# interface.net
KiCad netlist of a schematic drawn in EAGLE
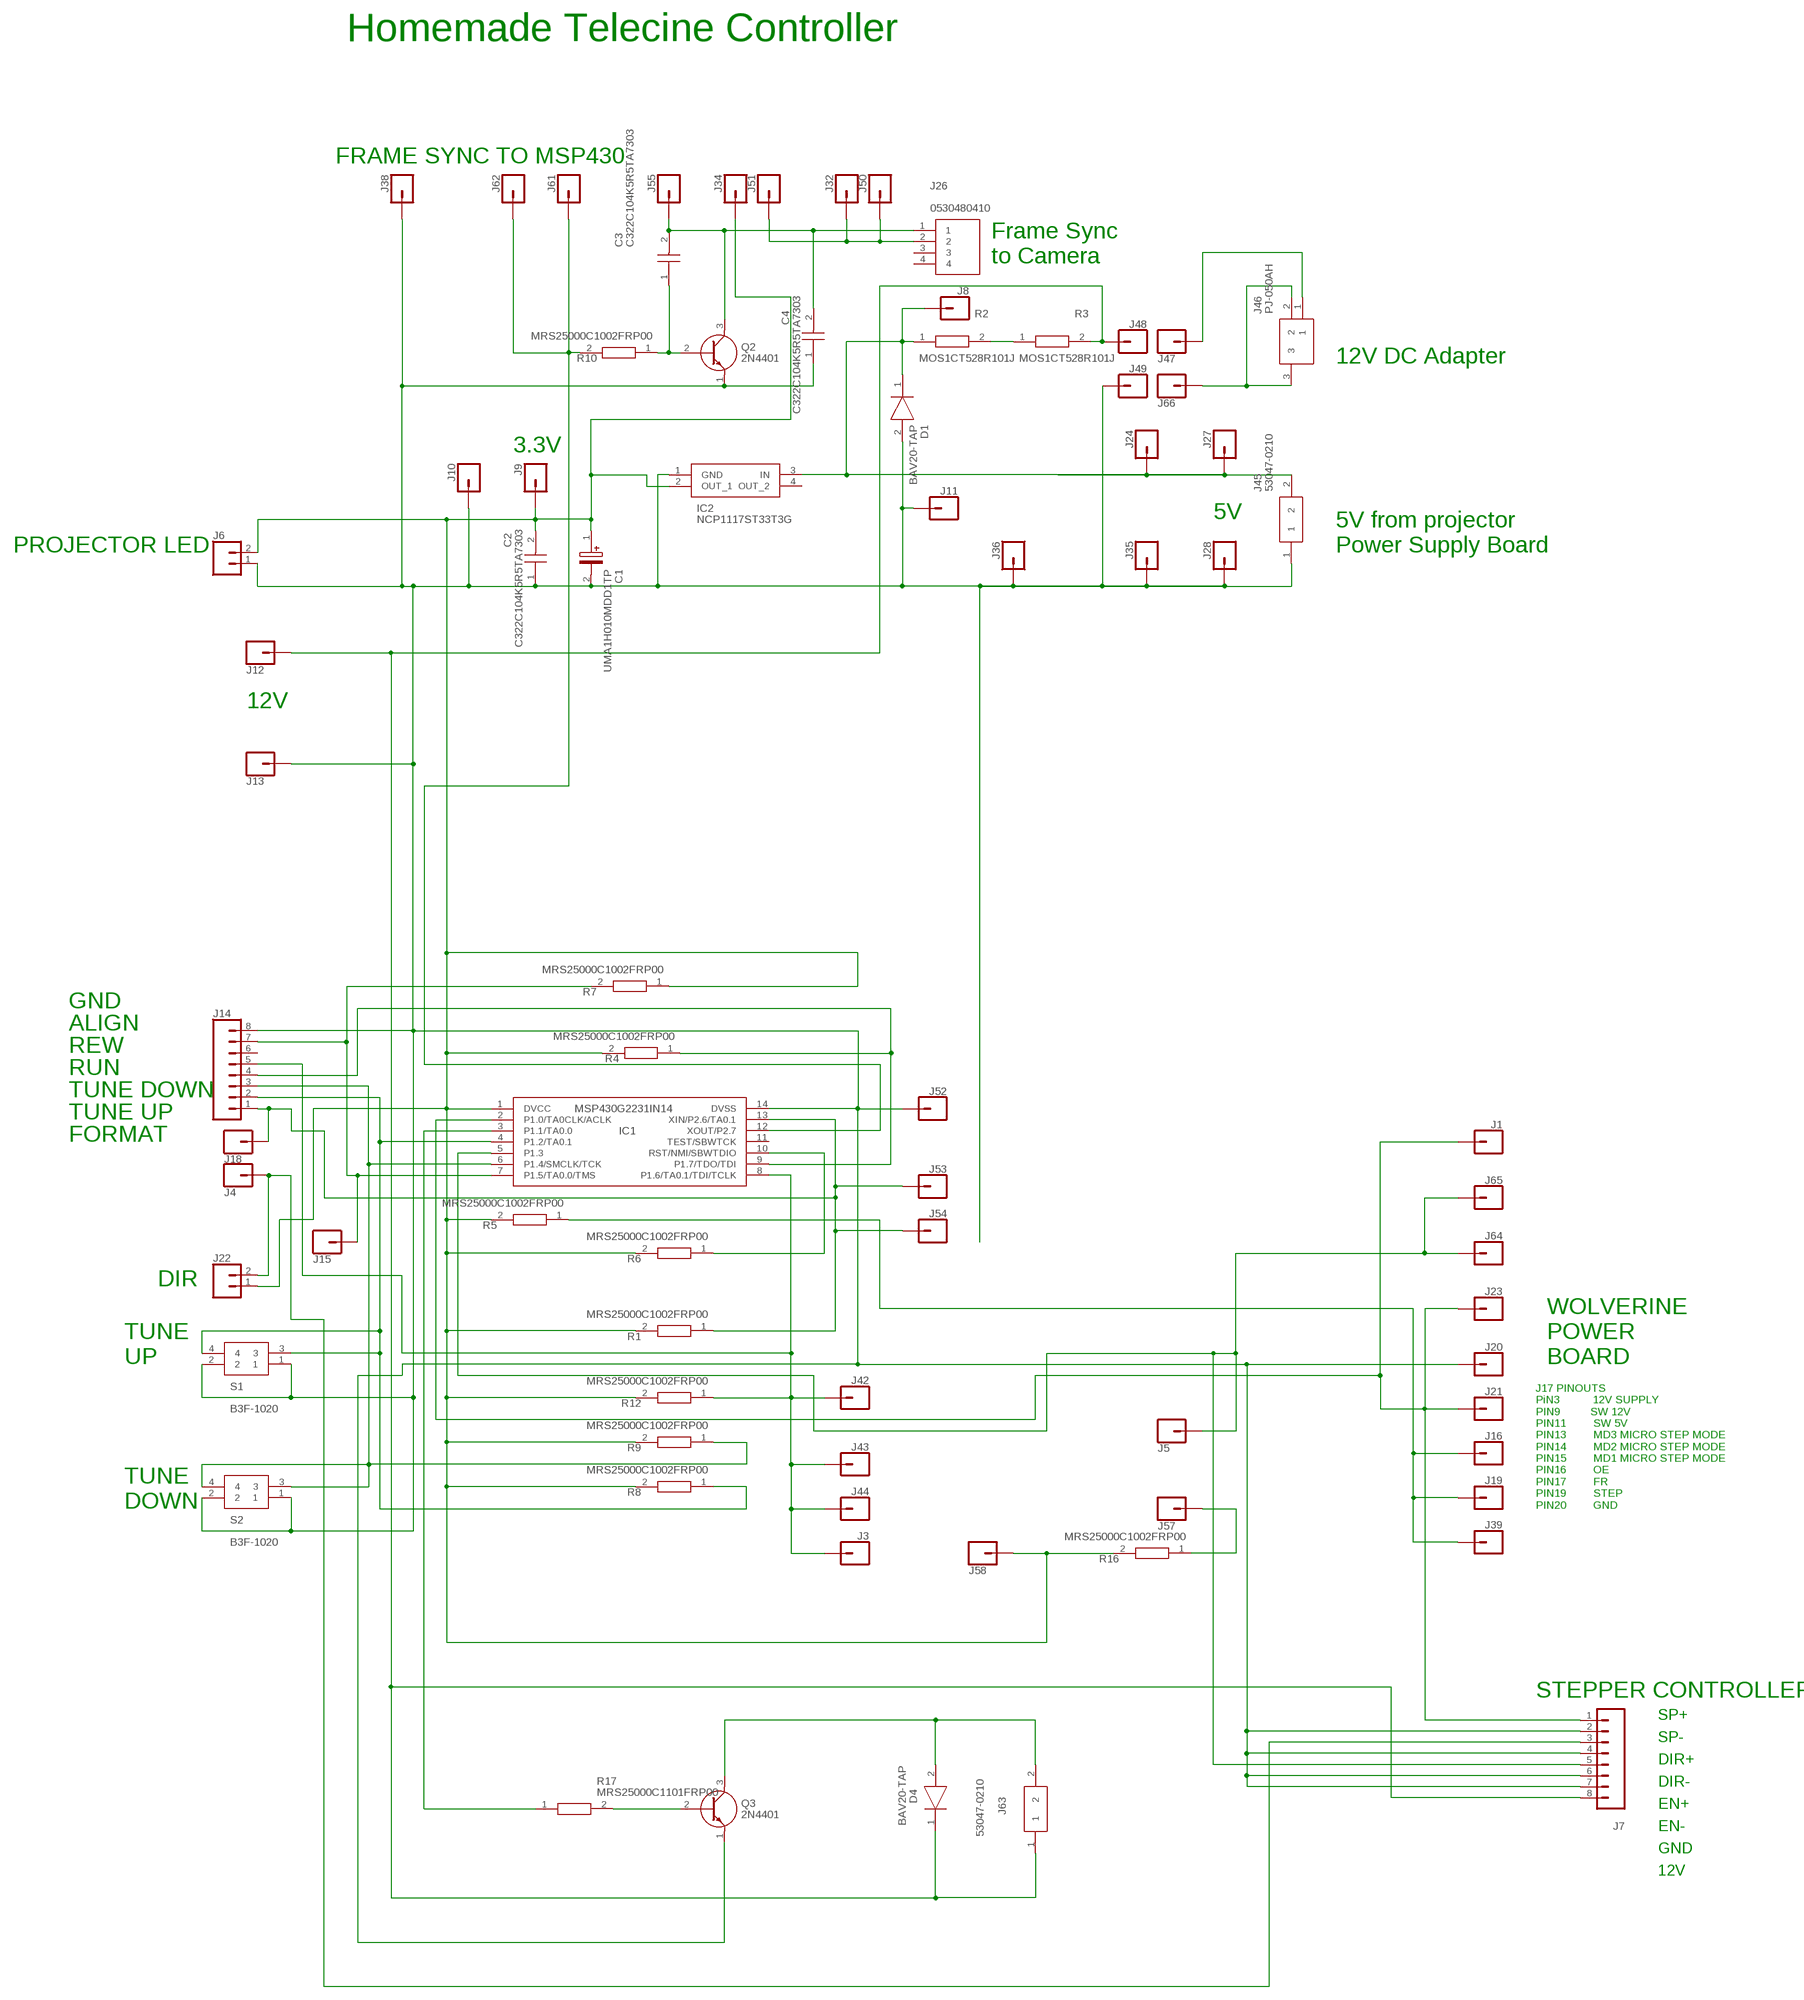
[diagram p0: schematic, sheet 1]

(export (version "E")
  (design (tool "Eeschema 10.0.6"))
  (components
    (comp (ref "C1")
      (value "UMA1H010MDD1TP")
      (footprint "eagle-import:CAPPRD150W45D450H600")
      (fields (field (name "MOUSER_PART_NUMBER") "647-UMA1H010MDD1TP"))
      (libsource (lib "eagle-import") (part "UMA1H010MDD1TP"))
    )
    (comp (ref "C2")
      (value "C322C104K5R5TA7303")
      (footprint "eagle-import:C322")
      (fields (field (name "MOUSER_PART_NUMBER") "80-C322C104K5R7303"))
      (libsource (lib "eagle-import") (part "C322C104K5R5TA7303"))
    )
    (comp (ref "C3")
      (value "C322C104K5R5TA7303")
      (footprint "eagle-import:C322")
      (fields (field (name "MOUSER_PART_NUMBER") "80-C322C104K5R7303"))
      (libsource (lib "eagle-import") (part "C322C104K5R5TA7303"))
    )
    (comp (ref "C4")
      (value "C322C104K5R5TA7303")
      (footprint "eagle-import:C322")
      (fields (field (name "MOUSER_PART_NUMBER") "80-C322C104K5R7303"))
      (libsource (lib "eagle-import") (part "C322C104K5R5TA7303"))
    )
    (comp (ref "D1")
      (value "BAV20-TAP")
      (footprint "eagle-import:DIOAD950W60L350D150")
      (fields (field (name "MOUSER_PART_NUMBER") "78-BAV20-TAP"))
      (libsource (lib "eagle-import") (part "BAV20-TAP"))
    )
    (comp (ref "D4")
      (value "BAV20-TAP")
      (footprint "eagle-import:DIOAD950W60L350D150")
      (fields (field (name "MOUSER_PART_NUMBER") "78-BAV20-TAP"))
      (libsource (lib "eagle-import") (part "BAV20-TAP"))
    )
    (comp (ref "IC1")
      (value "MSP430G2231IN14")
      (footprint "eagle-import:DIP254P762X508-14")
      (fields
        (field (name "MOUSER_PART_NUMBER") "595-MSP430G2231IN14")
        (field (name "RS_PART_NUMBER") "7244654P")
      )
      (libsource (lib "eagle-import") (part "MSP430G2231IN14"))
    )
    (comp (ref "IC2")
      (value "NCP1117ST33T3G")
      (footprint "eagle-import:SOT230P700X180-4N")
      (fields (field (name "MOUSER_PART_NUMBER") "863-NCP1117ST33T3G"))
      (libsource (lib "eagle-import") (part "NCP1117ST33T3G"))
    )
    (comp (ref "J1")
      (value "CONN_01")
      (footprint "eagle-import:1X01")
      (libsource (lib "eagle-import") (part "CONN_01"))
    )
    (comp (ref "J3")
      (value "CONN_01")
      (footprint "eagle-import:1X01")
      (libsource (lib "eagle-import") (part "CONN_01"))
    )
    (comp (ref "J4")
      (value "CONN_01")
      (footprint "eagle-import:1X01")
      (libsource (lib "eagle-import") (part "CONN_01"))
    )
    (comp (ref "J5")
      (value "CONN_01")
      (footprint "eagle-import:1X01")
      (libsource (lib "eagle-import") (part "CONN_01"))
    )
    (comp (ref "J6")
      (value "CONN_02")
      (footprint "eagle-import:1X02")
      (libsource (lib "eagle-import") (part "CONN_02"))
    )
    (comp (ref "J7")
      (value "CONN_08\"")
      (footprint "eagle-import:1X08")
      (libsource (lib "eagle-import") (part "CONN_08{dblquote}"))
    )
    (comp (ref "J8")
      (value "CONN_01")
      (footprint "eagle-import:1X01")
      (libsource (lib "eagle-import") (part "CONN_01"))
    )
    (comp (ref "J9")
      (value "CONN_01")
      (footprint "eagle-import:1X01")
      (libsource (lib "eagle-import") (part "CONN_01"))
    )
    (comp (ref "J10")
      (value "CONN_01")
      (footprint "eagle-import:1X01")
      (libsource (lib "eagle-import") (part "CONN_01"))
    )
    (comp (ref "J11")
      (value "CONN_01")
      (footprint "eagle-import:1X01")
      (libsource (lib "eagle-import") (part "CONN_01"))
    )
    (comp (ref "J12")
      (value "CONN_01")
      (footprint "eagle-import:1X01")
      (libsource (lib "eagle-import") (part "CONN_01"))
    )
    (comp (ref "J13")
      (value "CONN_01")
      (footprint "eagle-import:1X01")
      (libsource (lib "eagle-import") (part "CONN_01"))
    )
    (comp (ref "J14")
      (value "CONN_08\"")
      (footprint "eagle-import:1X08")
      (libsource (lib "eagle-import") (part "CONN_08{dblquote}"))
    )
    (comp (ref "J15")
      (value "CONN_01")
      (footprint "eagle-import:1X01")
      (libsource (lib "eagle-import") (part "CONN_01"))
    )
    (comp (ref "J16")
      (value "CONN_01")
      (footprint "eagle-import:1X01")
      (libsource (lib "eagle-import") (part "CONN_01"))
    )
    (comp (ref "J18")
      (value "CONN_01")
      (footprint "eagle-import:1X01")
      (libsource (lib "eagle-import") (part "CONN_01"))
    )
    (comp (ref "J19")
      (value "CONN_01")
      (footprint "eagle-import:1X01")
      (libsource (lib "eagle-import") (part "CONN_01"))
    )
    (comp (ref "J20")
      (value "CONN_01")
      (footprint "eagle-import:1X01")
      (libsource (lib "eagle-import") (part "CONN_01"))
    )
    (comp (ref "J21")
      (value "CONN_01")
      (footprint "eagle-import:1X01")
      (libsource (lib "eagle-import") (part "CONN_01"))
    )
    (comp (ref "J22")
      (value "CONN_02")
      (footprint "eagle-import:1X02")
      (libsource (lib "eagle-import") (part "CONN_02"))
    )
    (comp (ref "J23")
      (value "CONN_01")
      (footprint "eagle-import:1X01")
      (libsource (lib "eagle-import") (part "CONN_01"))
    )
    (comp (ref "J24")
      (value "CONN_01")
      (footprint "eagle-import:1X01")
      (libsource (lib "eagle-import") (part "CONN_01"))
    )
    (comp (ref "J26")
      (value "0530480410")
      (footprint "eagle-import:SHDR4W35P0X125_1X4_675X550X350")
      (libsource (lib "eagle-import") (part "0530480410"))
    )
    (comp (ref "J27")
      (value "CONN_01")
      (footprint "eagle-import:1X01")
      (libsource (lib "eagle-import") (part "CONN_01"))
    )
    (comp (ref "J28")
      (value "CONN_01")
      (footprint "eagle-import:1X01")
      (libsource (lib "eagle-import") (part "CONN_01"))
    )
    (comp (ref "J32")
      (value "CONN_01")
      (footprint "eagle-import:1X01")
      (libsource (lib "eagle-import") (part "CONN_01"))
    )
    (comp (ref "J34")
      (value "CONN_01")
      (footprint "eagle-import:1X01")
      (libsource (lib "eagle-import") (part "CONN_01"))
    )
    (comp (ref "J35")
      (value "CONN_01")
      (footprint "eagle-import:1X01")
      (libsource (lib "eagle-import") (part "CONN_01"))
    )
    (comp (ref "J36")
      (value "CONN_01")
      (footprint "eagle-import:1X01")
      (libsource (lib "eagle-import") (part "CONN_01"))
    )
    (comp (ref "J38")
      (value "CONN_01")
      (footprint "eagle-import:1X01")
      (libsource (lib "eagle-import") (part "CONN_01"))
    )
    (comp (ref "J39")
      (value "CONN_01")
      (footprint "eagle-import:1X01")
      (libsource (lib "eagle-import") (part "CONN_01"))
    )
    (comp (ref "J42")
      (value "CONN_01")
      (footprint "eagle-import:1X01")
      (libsource (lib "eagle-import") (part "CONN_01"))
    )
    (comp (ref "J43")
      (value "CONN_01")
      (footprint "eagle-import:1X01")
      (libsource (lib "eagle-import") (part "CONN_01"))
    )
    (comp (ref "J44")
      (value "CONN_01")
      (footprint "eagle-import:1X01")
      (libsource (lib "eagle-import") (part "CONN_01"))
    )
    (comp (ref "J45")
      (value "53047-0210")
      (footprint "eagle-import:53047-0210")
      (fields (field (name "RS_PART_NUMBER") "2799213P"))
      (libsource (lib "eagle-import") (part "53047-0210"))
    )
    (comp (ref "J46")
      (value "PJ-050AH")
      (footprint "eagle-import:PJ050AH")
      (fields (field (name "MOUSER_PART_NUMBER") "490-PJ-050AH"))
      (libsource (lib "eagle-import") (part "PJ-050AH"))
    )
    (comp (ref "J47")
      (value "CONN_01")
      (footprint "eagle-import:1X01")
      (libsource (lib "eagle-import") (part "CONN_01"))
    )
    (comp (ref "J48")
      (value "CONN_01")
      (footprint "eagle-import:1X01")
      (libsource (lib "eagle-import") (part "CONN_01"))
    )
    (comp (ref "J49")
      (value "CONN_01")
      (footprint "eagle-import:1X01")
      (libsource (lib "eagle-import") (part "CONN_01"))
    )
    (comp (ref "J50")
      (value "CONN_01")
      (footprint "eagle-import:1X01")
      (libsource (lib "eagle-import") (part "CONN_01"))
    )
    (comp (ref "J51")
      (value "CONN_01")
      (footprint "eagle-import:1X01")
      (libsource (lib "eagle-import") (part "CONN_01"))
    )
    (comp (ref "J52")
      (value "CONN_01")
      (footprint "eagle-import:1X01")
      (libsource (lib "eagle-import") (part "CONN_01"))
    )
    (comp (ref "J53")
      (value "CONN_01")
      (footprint "eagle-import:1X01")
      (libsource (lib "eagle-import") (part "CONN_01"))
    )
    (comp (ref "J54")
      (value "CONN_01")
      (footprint "eagle-import:1X01")
      (libsource (lib "eagle-import") (part "CONN_01"))
    )
    (comp (ref "J55")
      (value "CONN_01")
      (footprint "eagle-import:1X01")
      (libsource (lib "eagle-import") (part "CONN_01"))
    )
    (comp (ref "J57")
      (value "CONN_01")
      (footprint "eagle-import:1X01")
      (libsource (lib "eagle-import") (part "CONN_01"))
    )
    (comp (ref "J58")
      (value "CONN_01")
      (footprint "eagle-import:1X01")
      (libsource (lib "eagle-import") (part "CONN_01"))
    )
    (comp (ref "J61")
      (value "CONN_01")
      (footprint "eagle-import:1X01")
      (libsource (lib "eagle-import") (part "CONN_01"))
    )
    (comp (ref "J62")
      (value "CONN_01")
      (footprint "eagle-import:1X01")
      (libsource (lib "eagle-import") (part "CONN_01"))
    )
    (comp (ref "J63")
      (value "53047-0210")
      (footprint "eagle-import:53047-0210")
      (fields (field (name "RS_PART_NUMBER") "2799213P"))
      (libsource (lib "eagle-import") (part "53047-0210"))
    )
    (comp (ref "J64")
      (value "CONN_01")
      (footprint "eagle-import:1X01")
      (libsource (lib "eagle-import") (part "CONN_01"))
    )
    (comp (ref "J65")
      (value "CONN_01")
      (footprint "eagle-import:1X01")
      (libsource (lib "eagle-import") (part "CONN_01"))
    )
    (comp (ref "J66")
      (value "CONN_01")
      (footprint "eagle-import:1X01")
      (libsource (lib "eagle-import") (part "CONN_01"))
    )
    (comp (ref "Q2")
      (value "2N4401")
      (footprint "eagle-import:CS_TO-92")
      (fields (field (name "MOUSER_PART_NUMBER") "610-2N4401"))
      (libsource (lib "eagle-import") (part "2N4401"))
    )
    (comp (ref "Q3")
      (value "2N4401")
      (footprint "eagle-import:CS_TO-92")
      (fields (field (name "MOUSER_PART_NUMBER") "610-2N4401"))
      (libsource (lib "eagle-import") (part "2N4401"))
    )
    (comp (ref "R1")
      (value "MRS25000C1002FRP00")
      (footprint "eagle-import:RESAD1650W60L650D250")
      (fields (field (name "MOUSER_PART_NUMBER") "594-MRS2510K00F"))
      (libsource (lib "eagle-import") (part "MRS25000C1002FRP00"))
    )
    (comp (ref "R2")
      (value "MOS1CT528R101J")
      (footprint "eagle-import:RESAD2100W60L900D300")
      (fields (field (name "MOUSER_PART_NUMBER") "660-MOS1CT528R101J"))
      (libsource (lib "eagle-import") (part "MOS1CT528R101J"))
    )
    (comp (ref "R3")
      (value "MOS1CT528R101J")
      (footprint "eagle-import:RESAD2100W60L900D300")
      (fields (field (name "MOUSER_PART_NUMBER") "660-MOS1CT528R101J"))
      (libsource (lib "eagle-import") (part "MOS1CT528R101J"))
    )
    (comp (ref "R4")
      (value "MRS25000C1002FRP00")
      (footprint "eagle-import:RESAD1650W60L650D250")
      (fields (field (name "MOUSER_PART_NUMBER") "594-MRS2510K00F"))
      (libsource (lib "eagle-import") (part "MRS25000C1002FRP00"))
    )
    (comp (ref "R5")
      (value "MRS25000C1002FRP00")
      (footprint "eagle-import:RESAD1650W60L650D250")
      (fields (field (name "MOUSER_PART_NUMBER") "594-MRS2510K00F"))
      (libsource (lib "eagle-import") (part "MRS25000C1002FRP00"))
    )
    (comp (ref "R6")
      (value "MRS25000C1002FRP00")
      (footprint "eagle-import:RESAD1650W60L650D250")
      (fields (field (name "MOUSER_PART_NUMBER") "594-MRS2510K00F"))
      (libsource (lib "eagle-import") (part "MRS25000C1002FRP00"))
    )
    (comp (ref "R7")
      (value "MRS25000C1002FRP00")
      (footprint "eagle-import:RESAD1650W60L650D250")
      (fields (field (name "MOUSER_PART_NUMBER") "594-MRS2510K00F"))
      (libsource (lib "eagle-import") (part "MRS25000C1002FRP00"))
    )
    (comp (ref "R8")
      (value "MRS25000C1002FRP00")
      (footprint "eagle-import:RESAD1650W60L650D250")
      (fields (field (name "MOUSER_PART_NUMBER") "594-MRS2510K00F"))
      (libsource (lib "eagle-import") (part "MRS25000C1002FRP00"))
    )
    (comp (ref "R9")
      (value "MRS25000C1002FRP00")
      (footprint "eagle-import:RESAD1650W60L650D250")
      (fields (field (name "MOUSER_PART_NUMBER") "594-MRS2510K00F"))
      (libsource (lib "eagle-import") (part "MRS25000C1002FRP00"))
    )
    (comp (ref "R10")
      (value "MRS25000C1002FRP00")
      (footprint "eagle-import:RESAD1650W60L650D250")
      (fields (field (name "MOUSER_PART_NUMBER") "594-MRS2510K00F"))
      (libsource (lib "eagle-import") (part "MRS25000C1002FRP00"))
    )
    (comp (ref "R12")
      (value "MRS25000C1002FRP00")
      (footprint "eagle-import:RESAD1650W60L650D250")
      (fields (field (name "MOUSER_PART_NUMBER") "594-MRS2510K00F"))
      (libsource (lib "eagle-import") (part "MRS25000C1002FRP00"))
    )
    (comp (ref "R16")
      (value "MRS25000C1002FRP00")
      (footprint "eagle-import:RESAD1650W60L650D250")
      (fields (field (name "MOUSER_PART_NUMBER") "594-MRS2510K00F"))
      (libsource (lib "eagle-import") (part "MRS25000C1002FRP00"))
    )
    (comp (ref "R17")
      (value "MRS25000C1101FRP00")
      (footprint "eagle-import:RESAD1650W60L650D250")
      (fields (field (name "MOUSER_PART_NUMBER") "594-MRS25000C1101FRP"))
      (libsource (lib "eagle-import") (part "MRS25000C1101FRP00"))
    )
    (comp (ref "S1")
      (value "B3F-1020")
      (footprint "eagle-import:B3F1000")
      (fields (field (name "MOUSER_PART_NUMBER") "653-B3F-1020"))
      (libsource (lib "eagle-import") (part "B3F-1020"))
    )
    (comp (ref "S2")
      (value "B3F-1020")
      (footprint "eagle-import:B3F1000")
      (fields (field (name "MOUSER_PART_NUMBER") "653-B3F-1020"))
      (libsource (lib "eagle-import") (part "B3F-1020"))
    )
  )
  (nets
    (net (code "1") (name "Net-(C1-+)") (class "Default")
      (node (ref "C1") (pin "1") (pinfunction "+_1") (pintype "bidirectional"))
      (node (ref "C2") (pin "2") (pinfunction "2_2") (pintype "bidirectional"))
      (node (ref "IC1") (pin "1") (pinfunction "DVCC_1") (pintype "bidirectional"))
      (node (ref "IC2") (pin "2") (pinfunction "OUT_1_2") (pintype "output"))
      (node (ref "J22") (pin "1") (pinfunction "1_1") (pintype "passive"))
      (node (ref "J34") (pin "1") (pinfunction "1_1") (pintype "passive"))
      (node (ref "J58") (pin "1") (pinfunction "1_1") (pintype "passive"))
      (node (ref "J6") (pin "2") (pinfunction "2_2") (pintype "passive"))
      (node (ref "J9") (pin "1") (pinfunction "1_1") (pintype "passive"))
      (node (ref "R1") (pin "2") (pinfunction "2_2") (pintype "bidirectional"))
      (node (ref "R12") (pin "2") (pinfunction "2_2") (pintype "bidirectional"))
      (node (ref "R16") (pin "2") (pinfunction "2_2") (pintype "bidirectional"))
      (node (ref "R4") (pin "2") (pinfunction "2_2") (pintype "bidirectional"))
      (node (ref "R5") (pin "2") (pinfunction "2_2") (pintype "bidirectional"))
      (node (ref "R6") (pin "2") (pinfunction "2_2") (pintype "bidirectional"))
      (node (ref "R7") (pin "1") (pinfunction "1_1") (pintype "bidirectional"))
      (node (ref "R8") (pin "2") (pinfunction "2_2") (pintype "bidirectional"))
      (node (ref "R9") (pin "2") (pinfunction "2_2") (pintype "bidirectional"))
    )
    (net (code "2") (name "Net-(C1--)") (class "Default")
      (node (ref "C1") (pin "2") (pinfunction "-_2") (pintype "bidirectional"))
      (node (ref "C2") (pin "1") (pinfunction "1_1") (pintype "bidirectional"))
      (node (ref "C4") (pin "1") (pinfunction "1_1") (pintype "bidirectional"))
      (node (ref "D1") (pin "2") (pinfunction "A_2") (pintype "bidirectional"))
      (node (ref "IC1") (pin "14") (pinfunction "DVSS_14") (pintype "bidirectional"))
      (node (ref "IC2") (pin "1") (pinfunction "GND_1") (pintype "power_in"))
      (node (ref "J10") (pin "1") (pinfunction "1_1") (pintype "passive"))
      (node (ref "J11") (pin "1") (pinfunction "1_1") (pintype "passive"))
      (node (ref "J13") (pin "1") (pinfunction "1_1") (pintype "passive"))
      (node (ref "J14") (pin "8") (pinfunction "8_8") (pintype "passive"))
      (node (ref "J20") (pin "1") (pinfunction "1_1") (pintype "passive"))
      (node (ref "J28") (pin "1") (pinfunction "1_1") (pintype "passive"))
      (node (ref "J35") (pin "1") (pinfunction "1_1") (pintype "passive"))
      (node (ref "J36") (pin "1") (pinfunction "1_1") (pintype "passive"))
      (node (ref "J38") (pin "1") (pinfunction "1_1") (pintype "passive"))
      (node (ref "J45") (pin "1") (pinfunction "1_1") (pintype "bidirectional"))
      (node (ref "J49") (pin "1") (pinfunction "1_1") (pintype "passive"))
      (node (ref "J52") (pin "1") (pinfunction "1_1") (pintype "passive"))
      (node (ref "J6") (pin "1") (pinfunction "1_1") (pintype "passive"))
      (node (ref "J7") (pin "2") (pinfunction "2_2") (pintype "passive"))
      (node (ref "J7") (pin "4") (pinfunction "4_4") (pintype "passive"))
      (node (ref "J7") (pin "6") (pinfunction "6_6") (pintype "passive"))
      (node (ref "J7") (pin "7") (pinfunction "7_7") (pintype "passive"))
      (node (ref "Q2") (pin "1") (pinfunction "E_1") (pintype "bidirectional"))
      (node (ref "Q3") (pin "1") (pinfunction "E_1") (pintype "bidirectional"))
      (node (ref "S1") (pin "1") (pinfunction "1_1") (pintype "bidirectional"))
      (node (ref "S1") (pin "2") (pinfunction "2_2") (pintype "bidirectional"))
      (node (ref "S2") (pin "1") (pinfunction "1_1") (pintype "bidirectional"))
      (node (ref "S2") (pin "2") (pinfunction "2_2") (pintype "bidirectional"))
    )
    (net (code "3") (name "Net-(D1-K)") (class "Default")
      (node (ref "D1") (pin "1") (pinfunction "K_1") (pintype "bidirectional"))
      (node (ref "IC2") (pin "3") (pinfunction "IN_3") (pintype "input"))
      (node (ref "J24") (pin "1") (pinfunction "1_1") (pintype "passive"))
      (node (ref "J27") (pin "1") (pinfunction "1_1") (pintype "passive"))
      (node (ref "J45") (pin "2") (pinfunction "2_2") (pintype "bidirectional"))
      (node (ref "J8") (pin "1") (pinfunction "1_1") (pintype "passive"))
      (node (ref "R2") (pin "1") (pinfunction "1_1") (pintype "bidirectional"))
    )
    (net (code "4") (name "Net-(D4-A)") (class "Default")
      (node (ref "D4") (pin "2") (pinfunction "A_2") (pintype "bidirectional"))
      (node (ref "J63") (pin "2") (pinfunction "2_2") (pintype "bidirectional"))
      (node (ref "Q3") (pin "3") (pinfunction "C_3") (pintype "bidirectional"))
    )
    (net (code "5") (name "Net-(D4-K)") (class "Default")
      (node (ref "D4") (pin "1") (pinfunction "K_1") (pintype "bidirectional"))
      (node (ref "J12") (pin "1") (pinfunction "1_1") (pintype "passive"))
      (node (ref "J48") (pin "1") (pinfunction "1_1") (pintype "passive"))
      (node (ref "J63") (pin "1") (pinfunction "1_1") (pintype "bidirectional"))
      (node (ref "J7") (pin "8") (pinfunction "8_8") (pintype "passive"))
      (node (ref "R3") (pin "2") (pinfunction "2_2") (pintype "bidirectional"))
    )
    (net (code "6") (name "Net-(IC1-P1.0{slash}TA0CLK{slash}ACLK)") (class "Default")
      (node (ref "IC1") (pin "2") (pinfunction "P1.0/TA0CLK/ACLK_2") (pintype "bidirectional"))
      (node (ref "J1") (pin "1") (pinfunction "1_1") (pintype "passive"))
      (node (ref "J21") (pin "1") (pinfunction "1_1") (pintype "passive"))
      (node (ref "J23") (pin "1") (pinfunction "1_1") (pintype "passive"))
      (node (ref "J7") (pin "1") (pinfunction "1_1") (pintype "passive"))
    )
    (net (code "7") (name "Net-(IC1-P1.1{slash}TA0.0)") (class "Default")
      (node (ref "IC1") (pin "3") (pinfunction "P1.1/TA0.0_3") (pintype "bidirectional"))
      (node (ref "R17") (pin "1") (pinfunction "1_1") (pintype "bidirectional"))
    )
    (net (code "8") (name "Net-(IC1-P1.2{slash}TA0.1)") (class "Default")
      (node (ref "IC1") (pin "4") (pinfunction "P1.2/TA0.1_4") (pintype "bidirectional"))
      (node (ref "J14") (pin "2") (pinfunction "2_2") (pintype "passive"))
      (node (ref "R8") (pin "1") (pinfunction "1_1") (pintype "bidirectional"))
      (node (ref "S1") (pin "3") (pinfunction "3_3") (pintype "bidirectional"))
      (node (ref "S1") (pin "4") (pinfunction "4_4") (pintype "bidirectional"))
    )
    (net (code "9") (name "Net-(IC1-P1.3)") (class "Default")
      (node (ref "IC1") (pin "5") (pinfunction "P1.3_5") (pintype "bidirectional"))
      (node (ref "J5") (pin "1") (pinfunction "1_1") (pintype "passive"))
      (node (ref "J64") (pin "1") (pinfunction "1_1") (pintype "passive"))
      (node (ref "J65") (pin "1") (pinfunction "1_1") (pintype "passive"))
      (node (ref "J7") (pin "5") (pinfunction "5_5") (pintype "passive"))
    )
    (net (code "10") (name "Net-(IC1-P1.4{slash}SMCLK{slash}TCK)") (class "Default")
      (node (ref "IC1") (pin "6") (pinfunction "P1.4/SMCLK/TCK_6") (pintype "bidirectional"))
      (node (ref "J14") (pin "3") (pinfunction "3_3") (pintype "passive"))
      (node (ref "R9") (pin "1") (pinfunction "1_1") (pintype "bidirectional"))
      (node (ref "S2") (pin "3") (pinfunction "3_3") (pintype "bidirectional"))
      (node (ref "S2") (pin "4") (pinfunction "4_4") (pintype "bidirectional"))
    )
    (net (code "11") (name "Net-(IC1-P1.5{slash}TA0.0{slash}TMS)") (class "Default")
      (node (ref "IC1") (pin "7") (pinfunction "P1.5/TA0.0/TMS_7") (pintype "bidirectional"))
      (node (ref "J14") (pin "7") (pinfunction "7_7") (pintype "passive"))
      (node (ref "J15") (pin "1") (pinfunction "1_1") (pintype "passive"))
      (node (ref "R7") (pin "2") (pinfunction "2_2") (pintype "bidirectional"))
    )
    (net (code "12") (name "Net-(IC1-P1.6{slash}TA0.1{slash}TDI{slash}TCLK)") (class "Default")
      (node (ref "IC1") (pin "8") (pinfunction "P1.6/TA0.1/TDI/TCLK_8") (pintype "bidirectional"))
      (node (ref "J14") (pin "5") (pinfunction "5_5") (pintype "passive"))
      (node (ref "J3") (pin "1") (pinfunction "1_1") (pintype "passive"))
      (node (ref "J42") (pin "1") (pinfunction "1_1") (pintype "passive"))
      (node (ref "J43") (pin "1") (pinfunction "1_1") (pintype "passive"))
      (node (ref "J44") (pin "1") (pinfunction "1_1") (pintype "passive"))
      (node (ref "R12") (pin "1") (pinfunction "1_1") (pintype "bidirectional"))
    )
    (net (code "13") (name "Net-(IC1-P1.7{slash}TDO{slash}TDI)") (class "Default")
      (node (ref "IC1") (pin "9") (pinfunction "P1.7/TDO/TDI_9") (pintype "bidirectional"))
      (node (ref "J14") (pin "4") (pinfunction "4_4") (pintype "passive"))
      (node (ref "R4") (pin "1") (pinfunction "1_1") (pintype "bidirectional"))
    )
    (net (code "14") (name "Net-(IC1-RST{slash}NMI{slash}SBWTDIO)") (class "Default")
      (node (ref "IC1") (pin "10") (pinfunction "RST/NMI/SBWTDIO_10") (pintype "bidirectional"))
      (node (ref "R6") (pin "1") (pinfunction "1_1") (pintype "bidirectional"))
    )
    (net (code "15") (name "Net-(IC1-XIN{slash}P2.6{slash}TA0.1)") (class "Default")
      (node (ref "IC1") (pin "13") (pinfunction "XIN/P2.6/TA0.1_13") (pintype "bidirectional"))
      (node (ref "J14") (pin "1") (pinfunction "1_1") (pintype "passive"))
      (node (ref "J18") (pin "1") (pinfunction "1_1") (pintype "passive"))
      (node (ref "J53") (pin "1") (pinfunction "1_1") (pintype "passive"))
      (node (ref "J54") (pin "1") (pinfunction "1_1") (pintype "passive"))
      (node (ref "R1") (pin "1") (pinfunction "1_1") (pintype "bidirectional"))
    )
    (net (code "16") (name "Net-(IC1-XOUT{slash}P2.7)") (class "Default")
      (node (ref "IC1") (pin "12") (pinfunction "XOUT/P2.7_12") (pintype "bidirectional"))
      (node (ref "J61") (pin "1") (pinfunction "1_1") (pintype "passive"))
      (node (ref "J62") (pin "1") (pinfunction "1_1") (pintype "passive"))
      (node (ref "R10") (pin "2") (pinfunction "2_2") (pintype "bidirectional"))
    )
    (net (code "17") (name "Net-(J16-Pad1)") (class "Default")
      (node (ref "J16") (pin "1") (pinfunction "1_1") (pintype "passive"))
      (node (ref "J19") (pin "1") (pinfunction "1_1") (pintype "passive"))
      (node (ref "J39") (pin "1") (pinfunction "1_1") (pintype "passive"))
      (node (ref "R5") (pin "1") (pinfunction "1_1") (pintype "bidirectional"))
    )
    (net (code "18") (name "Net-(J22-Pad2)") (class "Default")
      (node (ref "J22") (pin "2") (pinfunction "2_2") (pintype "passive"))
      (node (ref "J4") (pin "1") (pinfunction "1_1") (pintype "passive"))
      (node (ref "J7") (pin "3") (pinfunction "3_3") (pintype "passive"))
    )
    (net (code "19") (name "Net-(J26-Pad2)") (class "Default")
      (node (ref "J26") (pin "2") (pinfunction "2_2") (pintype "bidirectional"))
      (node (ref "J32") (pin "1") (pinfunction "1_1") (pintype "passive"))
      (node (ref "J50") (pin "1") (pinfunction "1_1") (pintype "passive"))
      (node (ref "J51") (pin "1") (pinfunction "1_1") (pintype "passive"))
    )
    (net (code "20") (name "Net-(J46-Pad1)") (class "Default")
      (node (ref "J46") (pin "1") (pinfunction "1_1") (pintype "bidirectional"))
      (node (ref "J47") (pin "1") (pinfunction "1_1") (pintype "passive"))
    )
    (net (code "21") (name "Net-(J46-Pad2)") (class "Default")
      (node (ref "J46") (pin "2") (pinfunction "2_2") (pintype "bidirectional"))
      (node (ref "J46") (pin "3") (pinfunction "3_3") (pintype "bidirectional"))
      (node (ref "J66") (pin "1") (pinfunction "1_1") (pintype "passive"))
    )
    (net (code "22") (name "Net-(J57-Pad1)") (class "Default")
      (node (ref "J57") (pin "1") (pinfunction "1_1") (pintype "passive"))
      (node (ref "R16") (pin "1") (pinfunction "1_1") (pintype "bidirectional"))
    )
    (net (code "23") (name "Net-(Q2-B)") (class "Default")
      (node (ref "C3") (pin "1") (pinfunction "1_1") (pintype "bidirectional"))
      (node (ref "Q2") (pin "2") (pinfunction "B_2") (pintype "bidirectional"))
      (node (ref "R10") (pin "1") (pinfunction "1_1") (pintype "bidirectional"))
    )
    (net (code "24") (name "Net-(Q2-C)") (class "Default")
      (node (ref "C3") (pin "2") (pinfunction "2_2") (pintype "bidirectional"))
      (node (ref "C4") (pin "2") (pinfunction "2_2") (pintype "bidirectional"))
      (node (ref "J26") (pin "1") (pinfunction "1_1") (pintype "bidirectional"))
      (node (ref "J55") (pin "1") (pinfunction "1_1") (pintype "passive"))
      (node (ref "Q2") (pin "3") (pinfunction "C_3") (pintype "bidirectional"))
    )
    (net (code "25") (name "Net-(Q3-B)") (class "Default")
      (node (ref "Q3") (pin "2") (pinfunction "B_2") (pintype "bidirectional"))
      (node (ref "R17") (pin "2") (pinfunction "2_2") (pintype "bidirectional"))
    )
    (net (code "26") (name "Net-(R2-Pad2)") (class "Default")
      (node (ref "R2") (pin "2") (pinfunction "2_2") (pintype "bidirectional"))
      (node (ref "R3") (pin "1") (pinfunction "1_1") (pintype "bidirectional"))
    )
    (net (code "27") (name "unconnected-(IC1-TEST{slash}SBWTCK-Pad11)") (class "Default")
      (node (ref "IC1") (pin "11") (pinfunction "TEST/SBWTCK_11") (pintype "bidirectional"))
    )
    (net (code "28") (name "unconnected-(IC2-OUT_2-Pad4)") (class "Default")
      (node (ref "IC2") (pin "4") (pinfunction "OUT_2_4") (pintype "output"))
    )
    (net (code "29") (name "unconnected-(J14-Pad6)") (class "Default")
      (node (ref "J14") (pin "6") (pinfunction "6_6") (pintype "passive"))
    )
    (net (code "30") (name "unconnected-(J26-Pad3)") (class "Default")
      (node (ref "J26") (pin "3") (pinfunction "3_3") (pintype "bidirectional"))
    )
    (net (code "31") (name "unconnected-(J26-Pad4)") (class "Default")
      (node (ref "J26") (pin "4") (pinfunction "4_4") (pintype "bidirectional"))
    )
  )
)
